# analogSwitch.net
KiCad netlist of a schematic drawn in Altium Designer
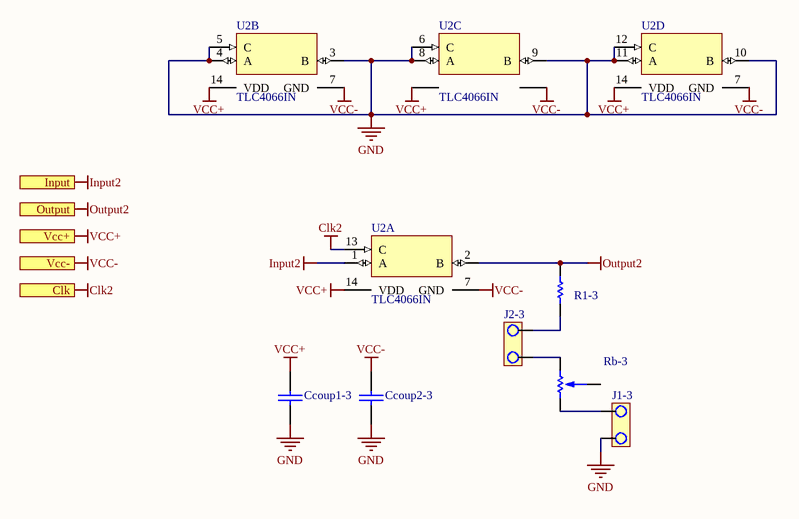
[diagram p0: analogSwitch.SchDoc]

(export (version "E")
  (design (tool "Eeschema 10.0.6"))
  (components
    (comp (ref "Ccoup1-3") (value "CAP") (footprint "CAP200") (libsource (lib "LIBEBAL") (part "CAP")))
    (comp (ref "Ccoup2-3") (value "CAP") (footprint "CAP200") (libsource (lib "LIBEBAL") (part "CAP")))
    (comp (ref "J1-3") (value "JUMPER") (footprint "JUMPER2") (libsource (lib "") (part "JUMPER_1")))
    (comp (ref "J2-3") (value "JUMPER") (footprint "JUMPER2") (libsource (lib "LIBEBAL") (part "JUMPER")))
    (comp (ref "R1-3")
      (value "Res1")
      (footprint "AXIAL-0.3")
      (description "Resistor")
      (fields (field (name "PUBLISHER") "Altium Limited"))
      (libsource (lib "Miscellaneous Devices") (part "Res1"))
    )
    (comp (ref "Rb-3") (value "PRESET") (footprint "PRESET V") (libsource (lib "LIBEBAL") (part "PRESET")))
    (comp (ref "U2")
      (value "TLC4066IN")
      (footprint "Texas Instruments Footprints:N014")
      (description "Quadruple Bilateral Analog Switch")
      (fields (field (name "PUBLISHER") "Altium Limited"))
      (libsource (lib "TI Logic Switch") (part "TLC4066IN"))
    )
  )
  (nets
    (net (code "1") (name "Clk2") (class "Default")
      (node (ref "U2") (pin "13") (pinfunction "C_13") (pintype "input"))
    )
    (net (code "2") (name "GND") (class "Default")
      (node (ref "Ccoup1-3") (pin "2") (pinfunction "2_2") (pintype "passive"))
      (node (ref "Ccoup2-3") (pin "1") (pinfunction "1_1") (pintype "passive"))
      (node (ref "Ccoup2-3") (pin "2") (pinfunction "2_2") (pintype "passive"))
      (node (ref "J1-3") (pin "1") (pinfunction "1_1") (pintype "passive"))
      (node (ref "U2") (pin "10") (pinfunction "B_10") (pintype "bidirectional"))
      (node (ref "U2") (pin "11") (pinfunction "A_11") (pintype "bidirectional"))
      (node (ref "U2") (pin "12") (pinfunction "C_12") (pintype "input"))
      (node (ref "U2") (pin "3") (pinfunction "B_3") (pintype "bidirectional"))
      (node (ref "U2") (pin "4") (pinfunction "A_4") (pintype "bidirectional"))
      (node (ref "U2") (pin "5") (pinfunction "C_5") (pintype "input"))
      (node (ref "U2") (pin "6") (pinfunction "C_6") (pintype "input"))
      (node (ref "U2") (pin "7") (pinfunction "GND_7") (pintype "power_in"))
      (node (ref "U2") (pin "8") (pinfunction "A_8") (pintype "bidirectional"))
      (node (ref "U2") (pin "9") (pinfunction "B_9") (pintype "bidirectional"))
    )
    (net (code "3") (name "Input2") (class "Default")
      (node (ref "U2") (pin "1") (pinfunction "A_1") (pintype "bidirectional"))
    )
    (net (code "4") (name "Net-(J1-3-Pad2)") (class "Default")
      (node (ref "J1-3") (pin "2") (pinfunction "2_2") (pintype "passive"))
      (node (ref "Rb-3") (pin "3") (pinfunction "3_3") (pintype "passive"))
    )
    (net (code "5") (name "Net-(J2-3-Pad1)") (class "Default")
      (node (ref "J2-3") (pin "1") (pinfunction "1_1") (pintype "passive"))
      (node (ref "R1-3") (pin "1") (pinfunction "1_1") (pintype "passive"))
    )
    (net (code "6") (name "Net-(J2-3-Pad2)") (class "Default")
      (node (ref "J2-3") (pin "2") (pinfunction "2_2") (pintype "passive"))
      (node (ref "Rb-3") (pin "1") (pinfunction "1_1") (pintype "passive"))
    )
    (net (code "7") (name "Output2") (class "Default")
      (node (ref "R1-3") (pin "2") (pinfunction "2_2") (pintype "passive"))
      (node (ref "U2") (pin "2") (pinfunction "B_2") (pintype "bidirectional"))
    )
    (net (code "8") (name "VCC+") (class "Default")
      (node (ref "Ccoup1-3") (pin "1") (pinfunction "1_1") (pintype "passive"))
      (node (ref "U2") (pin "14") (pinfunction "VDD_14") (pintype "power_in"))
    )
    (net (code "9") (name "unconnected-(Rb-3-Pad2)") (class "Default")
      (node (ref "Rb-3") (pin "2") (pinfunction "2_2") (pintype "passive"))
    )
  )
)
